# 6coils-1-discrete.net
KiCad netlist of a schematic drawn in EasyEDA
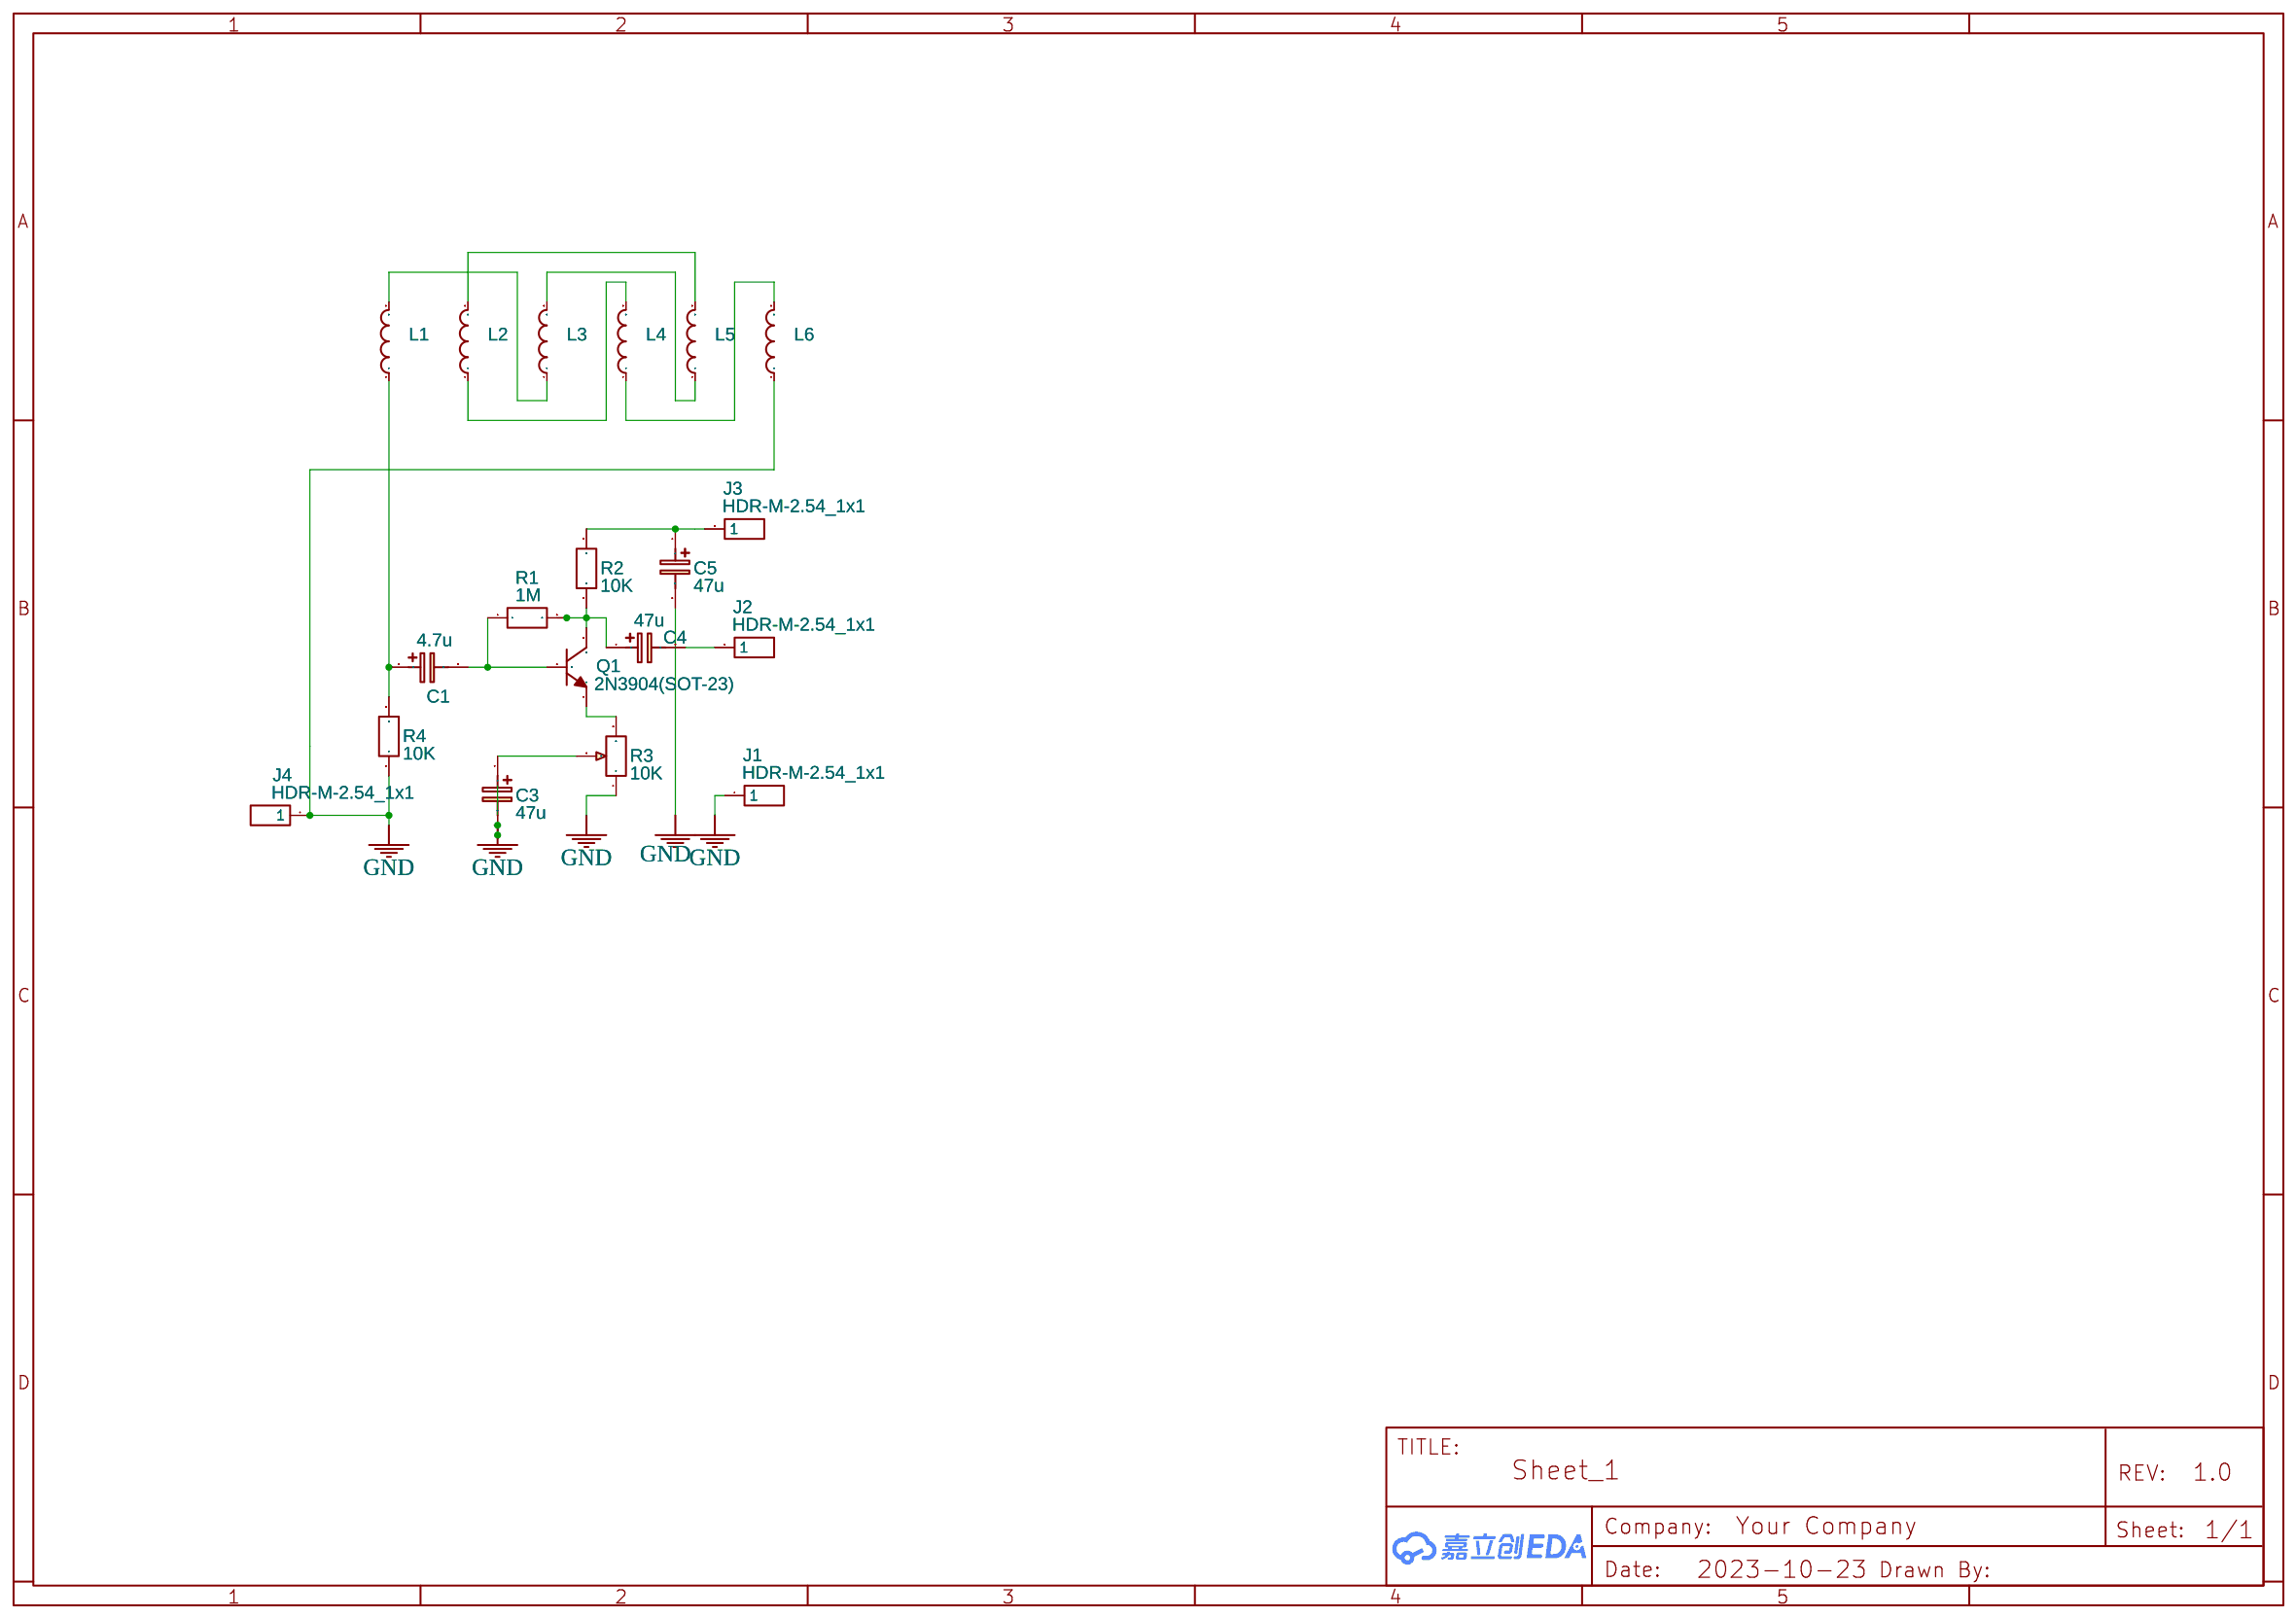
[diagram p0: schematic sheet]

(export (version "E")
  (design (tool "Eeschema 10.0.6"))
  (components
    (comp (ref "C1") (value "4.7u") (libsource (lib "") (part "C_Tan_SMD_A_EU")))
    (comp (ref "C3") (value "47u") (libsource (lib "") (part "C_Tan_SMD_A_EU_2")))
    (comp (ref "C4") (value "47u") (libsource (lib "") (part "C_Tan_SMD_A_EU_1")))
    (comp (ref "C5") (value "47u") (libsource (lib "") (part "C_Tan_SMD_A_EU_3")))
    (comp (ref "J1")
      (value "HDR-M-2.54_1x1")
      (fields (field (name "BOM_Supplier Part") "C81276"))
      (libsource (lib "") (part "HDR-M-2.54_1x1"))
    )
    (comp (ref "J2")
      (value "HDR-M-2.54_1x1")
      (fields (field (name "BOM_Supplier Part") "C81276"))
      (libsource (lib "") (part "HDR-M-2.54_1x1"))
    )
    (comp (ref "J3")
      (value "HDR-M-2.54_1x1")
      (fields (field (name "BOM_Supplier Part") "C81276"))
      (libsource (lib "") (part "HDR-M-2.54_1x1"))
    )
    (comp (ref "J4")
      (value "HDR-M-2.54_1x1")
      (fields (field (name "BOM_Supplier Part") "C81276"))
      (libsource (lib "") (part "HDR-M-2.54_1x1_1"))
    )
    (comp (ref "L1")
      (value "INDUCTOR_SMD:L_COILCRAFT_XXL4040")
      (fields (field (name "Manufacturer Part") "Inductor_SMD:L_Coilcraft_XxL4040"))
      (libsource (lib "") (part "INDUCTOR_SMD{colon}L_COILCRAFT_XXL4040_1"))
    )
    (comp (ref "L2")
      (value "INDUCTOR_SMD:L_COILCRAFT_XXL4040")
      (fields (field (name "Manufacturer Part") "Inductor_SMD:L_Coilcraft_XxL4040"))
      (libsource (lib "") (part "INDUCTOR_SMD{colon}L_COILCRAFT_XXL4040_1"))
    )
    (comp (ref "L3")
      (value "INDUCTOR_SMD:L_COILCRAFT_XXL4040")
      (fields (field (name "Manufacturer Part") "Inductor_SMD:L_Coilcraft_XxL4040"))
      (libsource (lib "") (part "INDUCTOR_SMD{colon}L_COILCRAFT_XXL4040"))
    )
    (comp (ref "L4")
      (value "INDUCTOR_SMD:L_COILCRAFT_XXL4040")
      (fields (field (name "Manufacturer Part") "Inductor_SMD:L_Coilcraft_XxL4040"))
      (libsource (lib "") (part "INDUCTOR_SMD{colon}L_COILCRAFT_XXL4040"))
    )
    (comp (ref "L5")
      (value "INDUCTOR_SMD:L_COILCRAFT_XXL4040")
      (fields (field (name "Manufacturer Part") "Inductor_SMD:L_Coilcraft_XxL4040"))
      (libsource (lib "") (part "INDUCTOR_SMD{colon}L_COILCRAFT_XXL4040"))
    )
    (comp (ref "L6")
      (value "INDUCTOR_SMD:L_COILCRAFT_XXL4040")
      (fields (field (name "Manufacturer Part") "Inductor_SMD:L_Coilcraft_XxL4040"))
      (libsource (lib "") (part "INDUCTOR_SMD{colon}L_COILCRAFT_XXL4040"))
    )
    (comp (ref "Q1")
      (value "2N3904(SOT-23)")
      (fields
        (field (name "BOM_Manufacturer Part") "2n3904S-RTK/PS")
        (field (name "BOM_Supplier Part") "C18536")
      )
      (libsource (lib "") (part "2N3904(SOT-23)"))
    )
    (comp (ref "R1") (value "1M") (libsource (lib "") (part "R_0603_EU")))
    (comp (ref "R2") (value "10K") (libsource (lib "") (part "R_0603_EU_1")))
    (comp (ref "R3")
      (value "10K")
      (fields (field (name "Manufacturer Part") "RM063-103 10K") (field (name "Manufacturer") "JML"))
      (libsource (lib "") (part "RM063-103 10K"))
    )
    (comp (ref "R4") (value "10K") (libsource (lib "") (part "R_0603_EU_1")))
  )
  (nets
    (net (code "1") (name "GND") (class "Default")
      (node (ref "C3") (pin "2") (pinfunction "2_2") (pintype "unspecified"))
      (node (ref "C5") (pin "2") (pinfunction "2_2") (pintype "unspecified"))
      (node (ref "J1") (pin "1") (pinfunction "1_1") (pintype "input"))
      (node (ref "J4") (pin "1") (pinfunction "1_1") (pintype "input"))
      (node (ref "L6") (pin "1") (pinfunction "1_1") (pintype "unspecified"))
      (node (ref "R3") (pin "1") (pinfunction "1_1") (pintype "input"))
      (node (ref "R4") (pin "1") (pinfunction "1_1") (pintype "unspecified"))
    )
    (net (code "2") (name "Net-(C1-Pad1)") (class "Default")
      (node (ref "C1") (pin "1") (pinfunction "1_1") (pintype "unspecified"))
      (node (ref "L1") (pin "1") (pinfunction "1_1") (pintype "unspecified"))
      (node (ref "R4") (pin "2") (pinfunction "2_2") (pintype "unspecified"))
    )
    (net (code "3") (name "Net-(C3-Pad1)") (class "Default")
      (node (ref "C3") (pin "1") (pinfunction "1_1") (pintype "unspecified"))
      (node (ref "R3") (pin "2") (pinfunction "2_2") (pintype "input"))
    )
    (net (code "4") (name "Net-(C4-Pad2)") (class "Default")
      (node (ref "C4") (pin "2") (pinfunction "2_2") (pintype "unspecified"))
      (node (ref "J2") (pin "1") (pinfunction "1_1") (pintype "input"))
    )
    (net (code "5") (name "Net-(C5-Pad1)") (class "Default")
      (node (ref "C5") (pin "1") (pinfunction "1_1") (pintype "unspecified"))
      (node (ref "J3") (pin "1") (pinfunction "1_1") (pintype "input"))
      (node (ref "R2") (pin "2") (pinfunction "2_2") (pintype "unspecified"))
    )
    (net (code "6") (name "Net-(L1-Pad2)") (class "Default")
      (node (ref "L1") (pin "2") (pinfunction "2_2") (pintype "unspecified"))
      (node (ref "L3") (pin "1") (pinfunction "1_1") (pintype "unspecified"))
    )
    (net (code "7") (name "Net-(L2-Pad1)") (class "Default")
      (node (ref "L2") (pin "1") (pinfunction "1_1") (pintype "unspecified"))
      (node (ref "L4") (pin "2") (pinfunction "2_2") (pintype "unspecified"))
    )
    (net (code "8") (name "Net-(L2-Pad2)") (class "Default")
      (node (ref "L2") (pin "2") (pinfunction "2_2") (pintype "unspecified"))
      (node (ref "L5") (pin "2") (pinfunction "2_2") (pintype "unspecified"))
    )
    (net (code "9") (name "Net-(L3-Pad2)") (class "Default")
      (node (ref "L3") (pin "2") (pinfunction "2_2") (pintype "unspecified"))
      (node (ref "L5") (pin "1") (pinfunction "1_1") (pintype "unspecified"))
    )
    (net (code "10") (name "Net-(L4-Pad1)") (class "Default")
      (node (ref "L4") (pin "1") (pinfunction "1_1") (pintype "unspecified"))
      (node (ref "L6") (pin "2") (pinfunction "2_2") (pintype "unspecified"))
    )
    (net (code "11") (name "Net-(Q1-B)") (class "Default")
      (node (ref "C1") (pin "2") (pinfunction "2_2") (pintype "unspecified"))
      (node (ref "Q1") (pin "2") (pinfunction "B_2") (pintype "input"))
      (node (ref "R1") (pin "1") (pinfunction "1_1") (pintype "unspecified"))
    )
    (net (code "12") (name "Net-(Q1-C)") (class "Default")
      (node (ref "C4") (pin "1") (pinfunction "1_1") (pintype "unspecified"))
      (node (ref "Q1") (pin "3") (pinfunction "C_3") (pintype "input"))
      (node (ref "R1") (pin "2") (pinfunction "2_2") (pintype "unspecified"))
      (node (ref "R2") (pin "1") (pinfunction "1_1") (pintype "unspecified"))
    )
    (net (code "13") (name "Net-(Q1-E)") (class "Default")
      (node (ref "Q1") (pin "1") (pinfunction "E_1") (pintype "input"))
      (node (ref "R3") (pin "3") (pinfunction "3_3") (pintype "input"))
    )
  )
)
